# FDD_3.net
KiCad netlist of a schematic drawn in Altium Designer
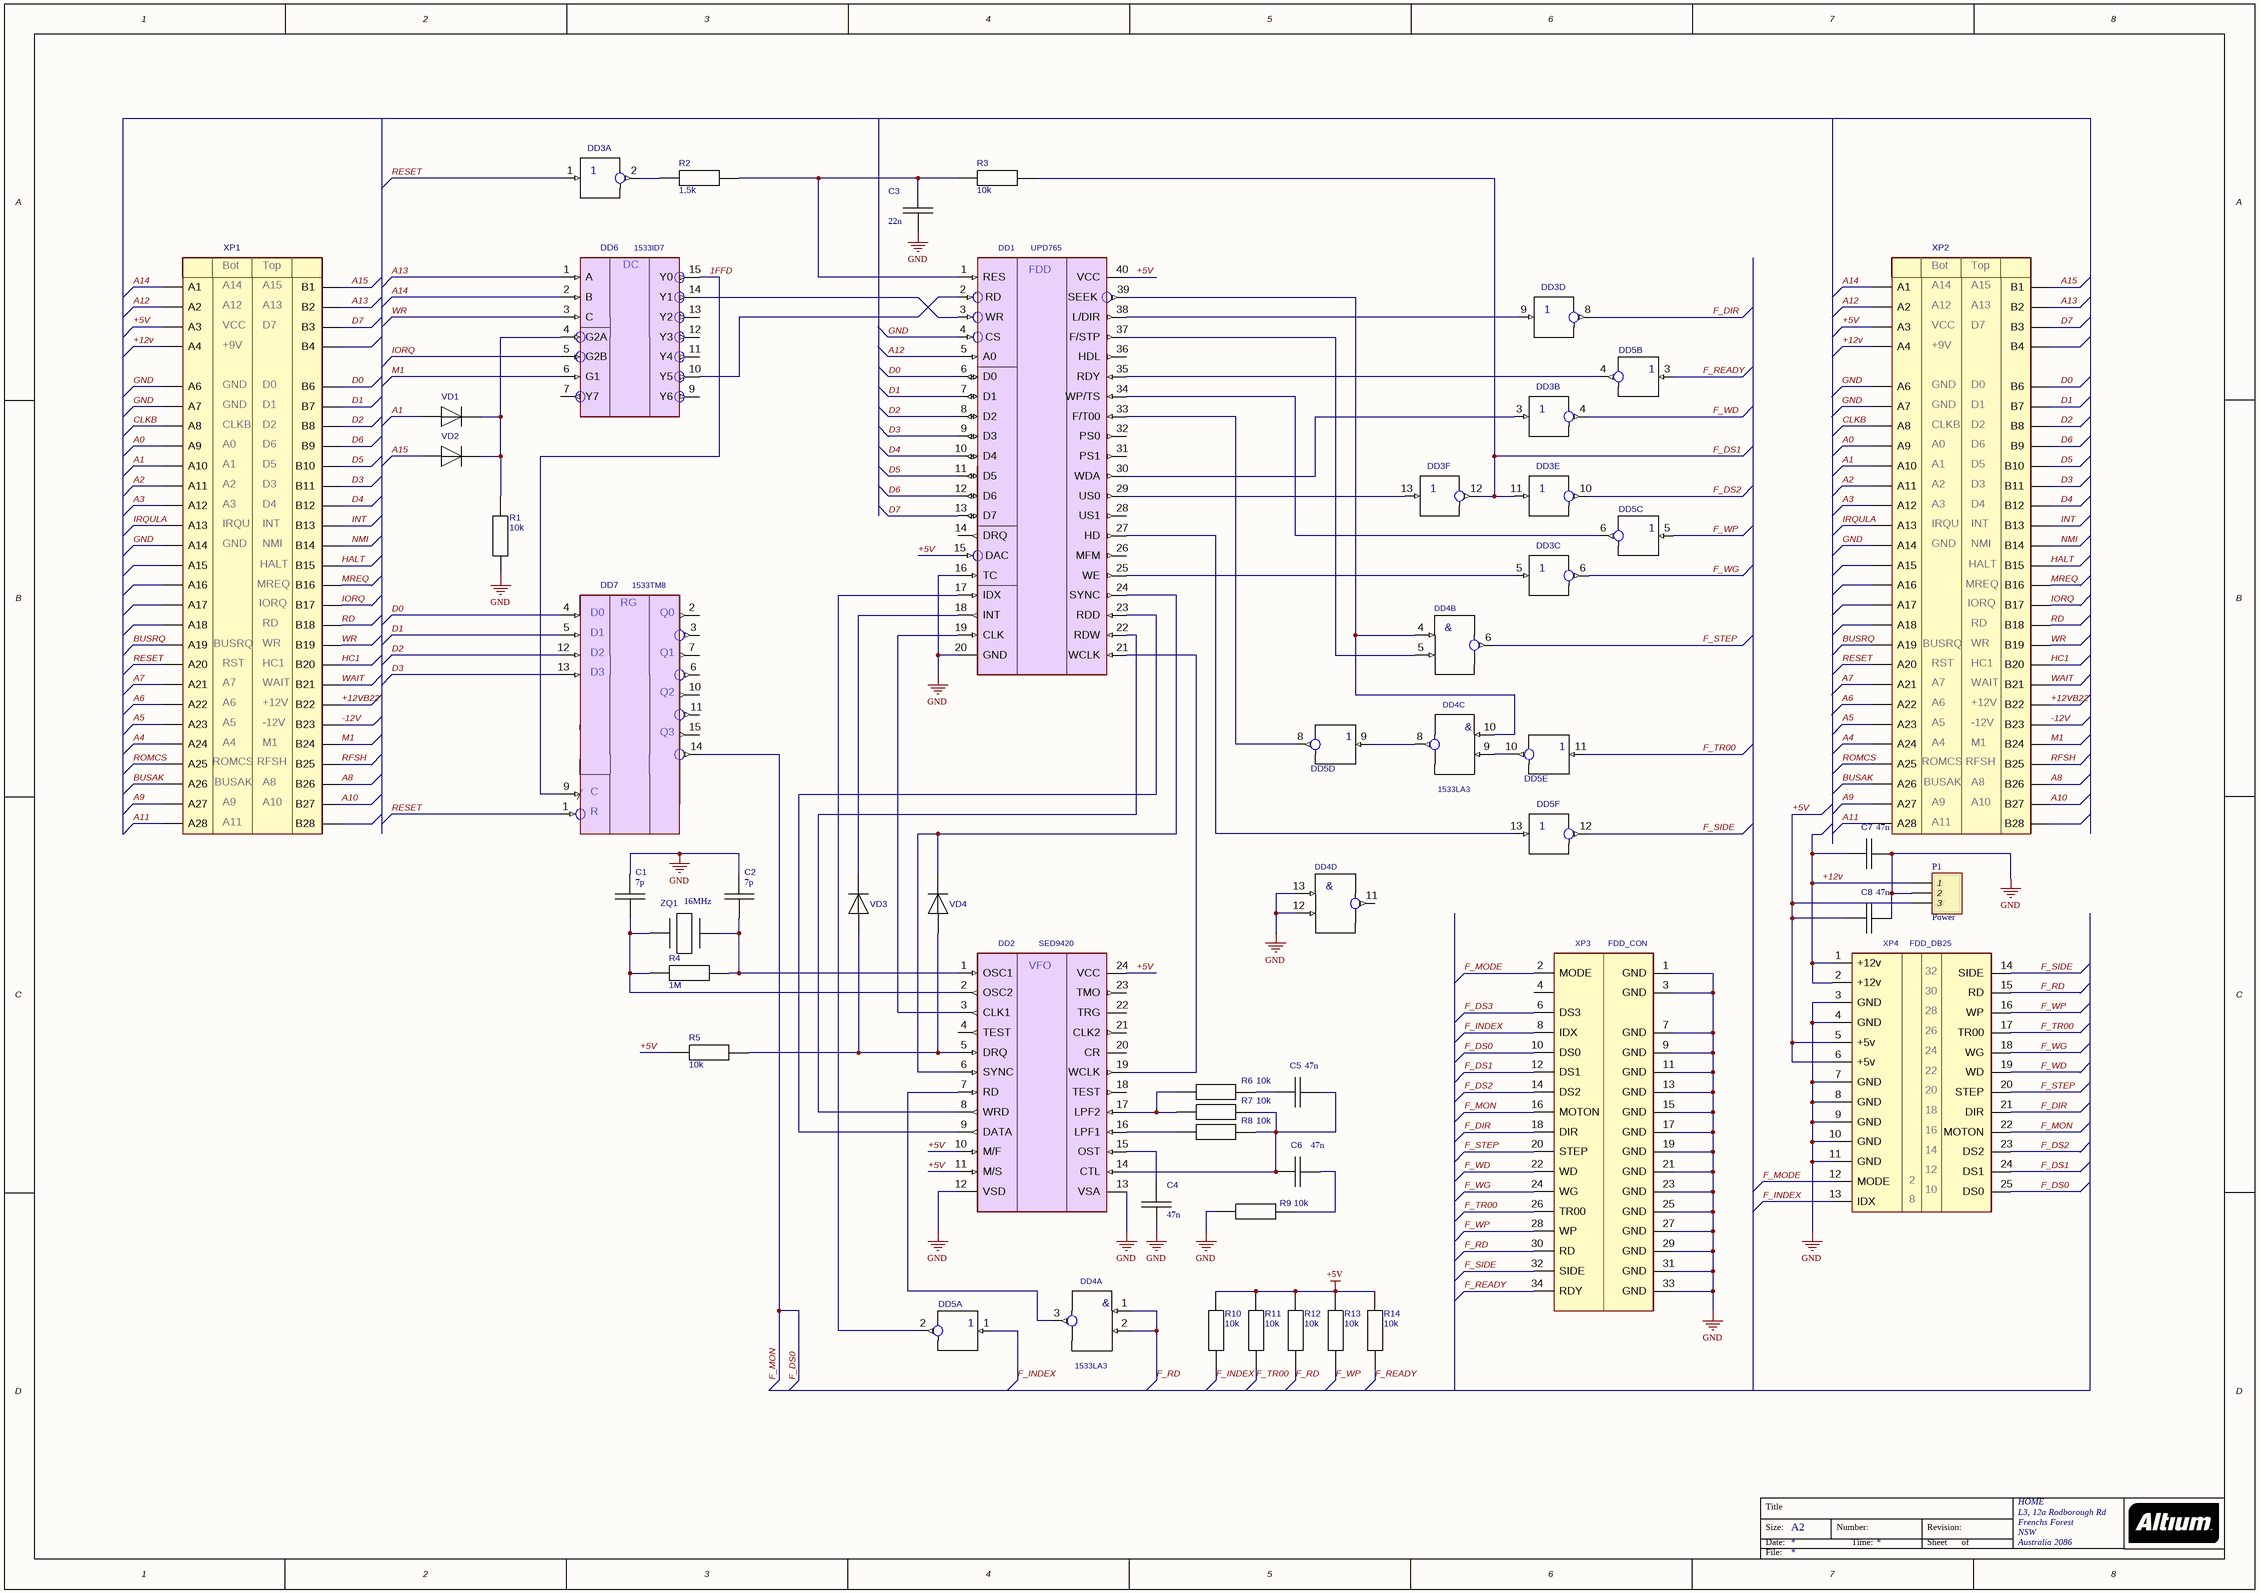
[diagram p0: FDD+3.SchDoc]

(export (version "E")
  (design (tool "Eeschema 10.0.6"))
  (components
    (comp (ref "C1")
      (value "7p")
      (footprint "K10-17_75")
      (fields (field (name "Comment") "K10-17_75"))
      (libsource (lib "Pentagon") (part "K10-17_75"))
    )
    (comp (ref "C2")
      (value "7p")
      (footprint "K10-17_75")
      (fields (field (name "Comment") "K10-17_75"))
      (libsource (lib "Pentagon") (part "K10-17_75"))
    )
    (comp (ref "C3")
      (value "22n")
      (footprint "K10-17_75")
      (fields (field (name "Comment") "K10-17_75"))
      (libsource (lib "Pentagon") (part "K10-17_75"))
    )
    (comp (ref "C4")
      (value "47n")
      (footprint "K10-17_75")
      (fields (field (name "Comment") "K10-17_75"))
      (libsource (lib "Pentagon") (part "K10-17_75"))
    )
    (comp (ref "C5")
      (value "47n")
      (footprint "K10-17_75")
      (fields (field (name "Comment") "K10-17_75"))
      (libsource (lib "Pentagon") (part "K10-17_75"))
    )
    (comp (ref "C6")
      (value "47n")
      (footprint "K10-17_75")
      (fields (field (name "Comment") "K10-17_75"))
      (libsource (lib "Pentagon") (part "K10-17_75"))
    )
    (comp (ref "C7")
      (value "47n")
      (footprint "K10-17_75")
      (fields (field (name "Comment") "K10-17_75"))
      (libsource (lib "Pentagon") (part "K10-17_75"))
    )
    (comp (ref "C8")
      (value "47n")
      (footprint "K10-17_75")
      (fields (field (name "Comment") "K10-17_75"))
      (libsource (lib "Pentagon") (part "K10-17_75"))
    )
    (comp (ref "DD1") (value "UPD765") (footprint "DIP40_15") (libsource (lib "Pentagon") (part "UPD765")))
    (comp (ref "DD2") (value "SED9420") (footprint "DIP24_15") (libsource (lib "Pentagon") (part "SED9420")))
    (comp (ref "DD3") (value "1533LN1") (footprint "DIP14") (libsource (lib "") (part "1533LN1_1")))
    (comp (ref "DD4") (value "1533LA3") (footprint "DIP14") (libsource (lib "Pentagon") (part "1533LA3")))
    (comp (ref "DD5") (value "1533LN1") (footprint "DIP14") (libsource (lib "") (part "1533LN1_5")))
    (comp (ref "DD6") (value "1533ID7") (footprint "DIP16") (libsource (lib "Pentagon") (part "1533ID7")))
    (comp (ref "DD7") (value "1533TM8") (footprint "DIP16") (libsource (lib "Pentagon") (part "1533TM8")))
    (comp (ref "P1")
      (value "Power")
      (footprint "HDR1X3")
      (description "Header, 3-Pin")
      (fields (field (name "PUBLISHER") "Altium Limited"))
      (libsource (lib "Miscellaneous Connectors") (part "Header 3"))
    )
    (comp (ref "R1")
      (value "10k")
      (footprint "R0125-2_5")
      (fields (field (name "Comment") "R0125-2_5"))
      (libsource (lib "Pentagon") (part "R0125-2_5"))
    )
    (comp (ref "R2")
      (value "1,5k")
      (footprint "R0125-2_5")
      (fields (field (name "Comment") "R0125-2_5"))
      (libsource (lib "Pentagon") (part "R0125-2_5"))
    )
    (comp (ref "R3")
      (value "10k")
      (footprint "R0125-2_5")
      (fields (field (name "Comment") "R0125-2_5"))
      (libsource (lib "Pentagon") (part "R0125-2_5"))
    )
    (comp (ref "R4")
      (value "1M")
      (footprint "R0125-2_5")
      (fields (field (name "Comment") "R0125-2_5"))
      (libsource (lib "Pentagon") (part "R0125-2_5"))
    )
    (comp (ref "R5")
      (value "10k")
      (footprint "R0125-2_5")
      (fields (field (name "Comment") "R0125-2_5"))
      (libsource (lib "Pentagon") (part "R0125-2_5"))
    )
    (comp (ref "R6")
      (value "10k")
      (footprint "R0125-2_5")
      (fields (field (name "Comment") "R0125-2_5"))
      (libsource (lib "Pentagon") (part "R0125-2_5"))
    )
    (comp (ref "R7")
      (value "10k")
      (footprint "R0125-2_5")
      (fields (field (name "Comment") "R0125-2_5"))
      (libsource (lib "Pentagon") (part "R0125-2_5"))
    )
    (comp (ref "R8")
      (value "10k")
      (footprint "R0125-2_5")
      (fields (field (name "Comment") "R0125-2_5"))
      (libsource (lib "Pentagon") (part "R0125-2_5"))
    )
    (comp (ref "R9")
      (value "10k")
      (footprint "R0125-2_5")
      (fields (field (name "Comment") "R0125-2_5"))
      (libsource (lib "Pentagon") (part "R0125-2_5"))
    )
    (comp (ref "R10")
      (value "10k")
      (footprint "R0125-2_5")
      (fields (field (name "Comment") "R0125-2_5"))
      (libsource (lib "Pentagon") (part "R0125-2_5"))
    )
    (comp (ref "R11")
      (value "10k")
      (footprint "R0125-2_5")
      (fields (field (name "Comment") "R0125-2_5"))
      (libsource (lib "Pentagon") (part "R0125-2_5"))
    )
    (comp (ref "R12")
      (value "10k")
      (footprint "R0125-2_5")
      (fields (field (name "Comment") "R0125-2_5"))
      (libsource (lib "Pentagon") (part "R0125-2_5"))
    )
    (comp (ref "R13")
      (value "10k")
      (footprint "R0125-2_5")
      (fields (field (name "Comment") "R0125-2_5"))
      (libsource (lib "Pentagon") (part "R0125-2_5"))
    )
    (comp (ref "R14")
      (value "10k")
      (footprint "R0125-2_5")
      (fields (field (name "Comment") "R0125-2_5"))
      (libsource (lib "Pentagon") (part "R0125-2_5"))
    )
    (comp (ref "VD1")
      (value "KD522-2_5")
      (footprint "KD522-2_5")
      (libsource (lib "Pentagon") (part "KD522-2_5"))
    )
    (comp (ref "VD2")
      (value "KD522-2_5")
      (footprint "KD522-2_5")
      (libsource (lib "Pentagon") (part "KD522-2_5"))
    )
    (comp (ref "VD3")
      (value "KD522-2_5")
      (footprint "KD522-2_5")
      (libsource (lib "Pentagon") (part "KD522-2_5"))
    )
    (comp (ref "VD4")
      (value "KD522-2_5")
      (footprint "KD522-2_5")
      (libsource (lib "Pentagon") (part "KD522-2_5"))
    )
    (comp (ref "XP1") (value "ZX EDGE") (footprint "ZX_EDGE") (libsource (lib "Pentagon") (part "ZX EDGE")))
    (comp (ref "XP2") (value "ZX EDGE") (footprint "ZX_EDGE") (libsource (lib "Pentagon") (part "ZX EDGE")))
    (comp (ref "XP3")
      (value "FDD_CON")
      (footprint "FDD_CON_Male")
      (libsource (lib "Pentagon") (part "FDD_CON"))
    )
    (comp (ref "XP4")
      (value "FDD_DB25")
      (footprint "DSUB1.385-2H25A")
      (libsource (lib "Pentagon") (part "FDD_DB25"))
    )
    (comp (ref "ZQ1")
      (value "16MHz")
      (footprint "RK169MD")
      (fields (field (name "Comment") "RK169MD"))
      (libsource (lib "Pentagon") (part "RK169MD"))
    )
  )
  (nets
    (net (code "1") (name "+5V") (class "Default")
      (node (ref "C8") (pin "2") (pinfunction "B_2") (pintype "passive"))
      (node (ref "DD1") (pin "15") (pinfunction "DAC_15") (pintype "input"))
      (node (ref "DD1") (pin "40") (pinfunction "VCC_40") (pintype "power_in"))
      (node (ref "DD2") (pin "10") (pinfunction "M/F_10") (pintype "input"))
      (node (ref "DD2") (pin "11") (pinfunction "M/S_11") (pintype "input"))
      (node (ref "DD2") (pin "24") (pinfunction "VCC_24") (pintype "power_in"))
      (node (ref "DD3") (pin "14") (pinfunction "+5V_14") (pintype "power_in"))
      (node (ref "DD4") (pin "14") (pinfunction "+5V_14") (pintype "power_in"))
      (node (ref "DD5") (pin "14") (pinfunction "+5V_14") (pintype "power_in"))
      (node (ref "DD6") (pin "16") (pinfunction "+5V_16") (pintype "power_in"))
      (node (ref "DD7") (pin "16") (pinfunction "+5V_16") (pintype "power_in"))
      (node (ref "P1") (pin "3") (pinfunction "3_3") (pintype "passive"))
      (node (ref "R10") (pin "1") (pinfunction "A_1") (pintype "passive"))
      (node (ref "R11") (pin "1") (pinfunction "A_1") (pintype "passive"))
      (node (ref "R12") (pin "1") (pinfunction "A_1") (pintype "passive"))
      (node (ref "R13") (pin "1") (pinfunction "A_1") (pintype "passive"))
      (node (ref "R14") (pin "1") (pinfunction "A_1") (pintype "passive"))
      (node (ref "R5") (pin "2") (pinfunction "B_2") (pintype "passive"))
      (node (ref "XP1") (pin "3") (pinfunction "A3_3") (pintype "power_in"))
      (node (ref "XP2") (pin "3") (pinfunction "A3_3") (pintype "power_in"))
      (node (ref "XP4") (pin "5") (pinfunction "+5v_5") (pintype "passive"))
      (node (ref "XP4") (pin "6") (pinfunction "+5v_6") (pintype "passive"))
    )
    (net (code "2") (name "/+12VB22") (class "Default")
      (node (ref "XP1") (pin "50") (pinfunction "B22_50") (pintype "passive"))
      (node (ref "XP2") (pin "50") (pinfunction "B22_50") (pintype "passive"))
    )
    (net (code "3") (name "/+12v") (class "Default")
      (node (ref "C7") (pin "2") (pinfunction "B_2") (pintype "passive"))
      (node (ref "P1") (pin "1") (pinfunction "1_1") (pintype "passive"))
      (node (ref "XP1") (pin "4") (pinfunction "A4_4") (pintype "passive"))
      (node (ref "XP2") (pin "4") (pinfunction "A4_4") (pintype "passive"))
      (node (ref "XP4") (pin "1") (pinfunction "+12v_1") (pintype "passive"))
      (node (ref "XP4") (pin "2") (pinfunction "+12v_2") (pintype "passive"))
    )
    (net (code "4") (name "/-12V") (class "Default")
      (node (ref "XP1") (pin "51") (pinfunction "B23_51") (pintype "passive"))
      (node (ref "XP2") (pin "51") (pinfunction "B23_51") (pintype "passive"))
    )
    (net (code "5") (name "/1FFD") (class "Default")
      (node (ref "DD6") (pin "15") (pinfunction "Y0_15") (pintype "output"))
      (node (ref "DD7") (pin "9") (pinfunction "C_9") (pintype "input"))
    )
    (net (code "6") (name "/A0") (class "Default")
      (node (ref "XP1") (pin "9") (pinfunction "A9_9") (pintype "passive"))
      (node (ref "XP2") (pin "9") (pinfunction "A9_9") (pintype "passive"))
    )
    (net (code "7") (name "/A1") (class "Default")
      (node (ref "VD1") (pin "1") (pinfunction "A_1") (pintype "passive"))
      (node (ref "XP1") (pin "10") (pinfunction "A10_10") (pintype "passive"))
      (node (ref "XP2") (pin "10") (pinfunction "A10_10") (pintype "passive"))
    )
    (net (code "8") (name "/A2") (class "Default")
      (node (ref "XP1") (pin "11") (pinfunction "A11_11") (pintype "passive"))
      (node (ref "XP2") (pin "11") (pinfunction "A11_11") (pintype "passive"))
    )
    (net (code "9") (name "/A3") (class "Default")
      (node (ref "XP1") (pin "12") (pinfunction "A12_12") (pintype "passive"))
      (node (ref "XP2") (pin "12") (pinfunction "A12_12") (pintype "passive"))
    )
    (net (code "10") (name "/A4") (class "Default")
      (node (ref "XP1") (pin "24") (pinfunction "A24_24") (pintype "passive"))
      (node (ref "XP2") (pin "24") (pinfunction "A24_24") (pintype "passive"))
    )
    (net (code "11") (name "/A5") (class "Default")
      (node (ref "XP1") (pin "23") (pinfunction "A23_23") (pintype "passive"))
      (node (ref "XP2") (pin "23") (pinfunction "A23_23") (pintype "passive"))
    )
    (net (code "12") (name "/A6") (class "Default")
      (node (ref "XP1") (pin "22") (pinfunction "A22_22") (pintype "passive"))
      (node (ref "XP2") (pin "22") (pinfunction "A22_22") (pintype "passive"))
    )
    (net (code "13") (name "/A7") (class "Default")
      (node (ref "XP1") (pin "21") (pinfunction "A21_21") (pintype "passive"))
      (node (ref "XP2") (pin "21") (pinfunction "A21_21") (pintype "passive"))
    )
    (net (code "14") (name "/A8") (class "Default")
      (node (ref "XP1") (pin "54") (pinfunction "B26_54") (pintype "passive"))
      (node (ref "XP2") (pin "54") (pinfunction "B26_54") (pintype "passive"))
    )
    (net (code "15") (name "/A9") (class "Default")
      (node (ref "XP1") (pin "27") (pinfunction "A27_27") (pintype "passive"))
      (node (ref "XP2") (pin "27") (pinfunction "A27_27") (pintype "passive"))
    )
    (net (code "16") (name "/A10") (class "Default")
      (node (ref "XP1") (pin "55") (pinfunction "B27_55") (pintype "passive"))
      (node (ref "XP2") (pin "55") (pinfunction "B27_55") (pintype "passive"))
    )
    (net (code "17") (name "/A11") (class "Default")
      (node (ref "XP1") (pin "28") (pinfunction "A28_28") (pintype "passive"))
      (node (ref "XP2") (pin "28") (pinfunction "A28_28") (pintype "passive"))
    )
    (net (code "18") (name "/A12") (class "Default")
      (node (ref "DD1") (pin "5") (pinfunction "A0_5") (pintype "input"))
      (node (ref "XP1") (pin "2") (pinfunction "A2_2") (pintype "passive"))
      (node (ref "XP2") (pin "2") (pinfunction "A2_2") (pintype "passive"))
    )
    (net (code "19") (name "/A13") (class "Default")
      (node (ref "DD6") (pin "1") (pinfunction "A_1") (pintype "input"))
      (node (ref "XP1") (pin "30") (pinfunction "B2_30") (pintype "passive"))
      (node (ref "XP2") (pin "30") (pinfunction "B2_30") (pintype "passive"))
    )
    (net (code "20") (name "/A14") (class "Default")
      (node (ref "DD6") (pin "2") (pinfunction "B_2") (pintype "input"))
      (node (ref "XP1") (pin "1") (pinfunction "A1_1") (pintype "passive"))
      (node (ref "XP2") (pin "1") (pinfunction "A1_1") (pintype "passive"))
    )
    (net (code "21") (name "/A15") (class "Default")
      (node (ref "VD2") (pin "1") (pinfunction "A_1") (pintype "passive"))
      (node (ref "XP1") (pin "29") (pinfunction "B1_29") (pintype "passive"))
      (node (ref "XP2") (pin "29") (pinfunction "B1_29") (pintype "passive"))
    )
    (net (code "22") (name "/BUSAK") (class "Default")
      (node (ref "XP1") (pin "26") (pinfunction "A26_26") (pintype "passive"))
      (node (ref "XP2") (pin "26") (pinfunction "A26_26") (pintype "passive"))
    )
    (net (code "23") (name "/BUSRQ") (class "Default")
      (node (ref "XP1") (pin "19") (pinfunction "A19_19") (pintype "passive"))
      (node (ref "XP2") (pin "19") (pinfunction "A19_19") (pintype "passive"))
    )
    (net (code "24") (name "/CLKB") (class "Default")
      (node (ref "XP1") (pin "8") (pinfunction "A8_8") (pintype "passive"))
      (node (ref "XP2") (pin "8") (pinfunction "A8_8") (pintype "passive"))
    )
    (net (code "25") (name "/D0") (class "Default")
      (node (ref "DD1") (pin "6") (pinfunction "D0_6") (pintype "bidirectional"))
      (node (ref "DD7") (pin "4") (pinfunction "D0_4") (pintype "input"))
      (node (ref "XP1") (pin "34") (pinfunction "B6_34") (pintype "passive"))
      (node (ref "XP2") (pin "34") (pinfunction "B6_34") (pintype "passive"))
    )
    (net (code "26") (name "/D1") (class "Default")
      (node (ref "DD1") (pin "7") (pinfunction "D1_7") (pintype "bidirectional"))
      (node (ref "DD7") (pin "5") (pinfunction "D1_5") (pintype "input"))
      (node (ref "XP1") (pin "35") (pinfunction "B7_35") (pintype "passive"))
      (node (ref "XP2") (pin "35") (pinfunction "B7_35") (pintype "passive"))
    )
    (net (code "27") (name "/D2") (class "Default")
      (node (ref "DD1") (pin "8") (pinfunction "D2_8") (pintype "bidirectional"))
      (node (ref "DD7") (pin "12") (pinfunction "D2_12") (pintype "input"))
      (node (ref "XP1") (pin "36") (pinfunction "B8_36") (pintype "passive"))
      (node (ref "XP2") (pin "36") (pinfunction "B8_36") (pintype "passive"))
    )
    (net (code "28") (name "/D3") (class "Default")
      (node (ref "DD1") (pin "9") (pinfunction "D3_9") (pintype "bidirectional"))
      (node (ref "DD7") (pin "13") (pinfunction "D3_13") (pintype "input"))
      (node (ref "XP1") (pin "39") (pinfunction "B11_39") (pintype "passive"))
      (node (ref "XP2") (pin "39") (pinfunction "B11_39") (pintype "passive"))
    )
    (net (code "29") (name "/D4") (class "Default")
      (node (ref "DD1") (pin "10") (pinfunction "D4_10") (pintype "bidirectional"))
      (node (ref "XP1") (pin "40") (pinfunction "B12_40") (pintype "passive"))
      (node (ref "XP2") (pin "40") (pinfunction "B12_40") (pintype "passive"))
    )
    (net (code "30") (name "/D5") (class "Default")
      (node (ref "DD1") (pin "11") (pinfunction "D5_11") (pintype "bidirectional"))
      (node (ref "XP1") (pin "38") (pinfunction "B10_38") (pintype "passive"))
      (node (ref "XP2") (pin "38") (pinfunction "B10_38") (pintype "passive"))
    )
    (net (code "31") (name "/D6") (class "Default")
      (node (ref "DD1") (pin "12") (pinfunction "D6_12") (pintype "bidirectional"))
      (node (ref "XP1") (pin "37") (pinfunction "B9_37") (pintype "passive"))
      (node (ref "XP2") (pin "37") (pinfunction "B9_37") (pintype "passive"))
    )
    (net (code "32") (name "/D7") (class "Default")
      (node (ref "DD1") (pin "13") (pinfunction "D7_13") (pintype "bidirectional"))
      (node (ref "XP1") (pin "31") (pinfunction "B3_31") (pintype "passive"))
      (node (ref "XP2") (pin "31") (pinfunction "B3_31") (pintype "passive"))
    )
    (net (code "33") (name "/F_DIR") (class "Default")
      (node (ref "DD3") (pin "8") (pinfunction "B_8") (pintype "output"))
      (node (ref "XP3") (pin "18") (pinfunction "DIR_18") (pintype "passive"))
      (node (ref "XP4") (pin "21") (pinfunction "DIR_21") (pintype "passive"))
    )
    (net (code "34") (name "/F_DS0") (class "Default")
      (node (ref "DD7") (pin "14") (pinfunction "Q4/_14") (pintype "output"))
      (node (ref "XP3") (pin "10") (pinfunction "DS0_10") (pintype "passive"))
      (node (ref "XP3") (pin "16") (pinfunction "MOTON_16") (pintype "passive"))
      (node (ref "XP4") (pin "22") (pinfunction "MOTON_22") (pintype "passive"))
      (node (ref "XP4") (pin "25") (pinfunction "DS0_25") (pintype "passive"))
    )
    (net (code "35") (name "/F_DS1") (class "Default")
      (node (ref "DD3") (pin "11") (pinfunction "A_11") (pintype "input"))
      (node (ref "DD3") (pin "12") (pinfunction "B_12") (pintype "output"))
      (node (ref "R3") (pin "1") (pinfunction "A_1") (pintype "passive"))
      (node (ref "XP3") (pin "12") (pinfunction "DS1_12") (pintype "passive"))
      (node (ref "XP4") (pin "24") (pinfunction "DS1_24") (pintype "passive"))
    )
    (net (code "36") (name "/F_DS2") (class "Default")
      (node (ref "DD3") (pin "10") (pinfunction "B_10") (pintype "output"))
      (node (ref "XP3") (pin "14") (pinfunction "DS2_14") (pintype "passive"))
      (node (ref "XP4") (pin "23") (pinfunction "DS2_23") (pintype "passive"))
    )
    (net (code "37") (name "/F_DS3") (class "Default")
      (node (ref "XP3") (pin "6") (pinfunction "DS3_6") (pintype "passive"))
    )
    (net (code "38") (name "/F_INDEX") (class "Default")
      (node (ref "DD5") (pin "1") (pinfunction "A_1") (pintype "input"))
      (node (ref "R10") (pin "2") (pinfunction "B_2") (pintype "passive"))
      (node (ref "XP3") (pin "8") (pinfunction "IDX_8") (pintype "passive"))
      (node (ref "XP4") (pin "13") (pinfunction "IDX_13") (pintype "passive"))
    )
    (net (code "39") (name "/F_MODE") (class "Default")
      (node (ref "XP3") (pin "2") (pinfunction "MODE_2") (pintype "passive"))
      (node (ref "XP4") (pin "12") (pinfunction "MODE_12") (pintype "passive"))
    )
    (net (code "40") (name "/F_RD") (class "Default")
      (node (ref "DD4") (pin "1") (pinfunction "A_1") (pintype "input"))
      (node (ref "DD4") (pin "2") (pinfunction "B_2") (pintype "input"))
      (node (ref "R12") (pin "2") (pinfunction "B_2") (pintype "passive"))
      (node (ref "XP3") (pin "30") (pinfunction "RD_30") (pintype "passive"))
      (node (ref "XP4") (pin "15") (pinfunction "RD_15") (pintype "passive"))
    )
    (net (code "41") (name "/F_READY") (class "Default")
      (node (ref "DD5") (pin "3") (pinfunction "A_3") (pintype "input"))
      (node (ref "R14") (pin "2") (pinfunction "B_2") (pintype "passive"))
      (node (ref "XP3") (pin "34") (pinfunction "RDY_34") (pintype "passive"))
    )
    (net (code "42") (name "/F_SIDE") (class "Default")
      (node (ref "DD5") (pin "12") (pinfunction "B_12") (pintype "output"))
      (node (ref "XP3") (pin "32") (pinfunction "SIDE_32") (pintype "passive"))
      (node (ref "XP4") (pin "14") (pinfunction "SIDE_14") (pintype "passive"))
    )
    (net (code "43") (name "/F_STEP") (class "Default")
      (node (ref "DD4") (pin "6") (pinfunction "C_6") (pintype "output"))
      (node (ref "XP3") (pin "20") (pinfunction "STEP_20") (pintype "passive"))
      (node (ref "XP4") (pin "20") (pinfunction "STEP_20") (pintype "passive"))
    )
    (net (code "44") (name "/F_TR00") (class "Default")
      (node (ref "DD5") (pin "11") (pinfunction "A_11") (pintype "input"))
      (node (ref "R11") (pin "2") (pinfunction "B_2") (pintype "passive"))
      (node (ref "XP3") (pin "26") (pinfunction "TR00_26") (pintype "passive"))
      (node (ref "XP4") (pin "17") (pinfunction "TR00_17") (pintype "passive"))
    )
    (net (code "45") (name "/F_WD") (class "Default")
      (node (ref "DD3") (pin "4") (pinfunction "B_4") (pintype "output"))
      (node (ref "XP3") (pin "22") (pinfunction "WD_22") (pintype "passive"))
      (node (ref "XP4") (pin "19") (pinfunction "WD_19") (pintype "passive"))
    )
    (net (code "46") (name "/F_WG") (class "Default")
      (node (ref "DD3") (pin "6") (pinfunction "B_6") (pintype "output"))
      (node (ref "XP3") (pin "24") (pinfunction "WG_24") (pintype "passive"))
      (node (ref "XP4") (pin "18") (pinfunction "WG_18") (pintype "passive"))
    )
    (net (code "47") (name "/F_WP") (class "Default")
      (node (ref "DD5") (pin "5") (pinfunction "A_5") (pintype "input"))
      (node (ref "R13") (pin "2") (pinfunction "B_2") (pintype "passive"))
      (node (ref "XP3") (pin "28") (pinfunction "WP_28") (pintype "passive"))
      (node (ref "XP4") (pin "16") (pinfunction "WP_16") (pintype "passive"))
    )
    (net (code "48") (name "/HALT") (class "Default")
      (node (ref "XP1") (pin "43") (pinfunction "B15_43") (pintype "passive"))
      (node (ref "XP2") (pin "43") (pinfunction "B15_43") (pintype "passive"))
    )
    (net (code "49") (name "/HC1") (class "Default")
      (node (ref "XP1") (pin "48") (pinfunction "B20_48") (pintype "passive"))
      (node (ref "XP2") (pin "48") (pinfunction "B20_48") (pintype "passive"))
    )
    (net (code "50") (name "/INT") (class "Default")
      (node (ref "XP1") (pin "41") (pinfunction "B13_41") (pintype "passive"))
      (node (ref "XP2") (pin "41") (pinfunction "B13_41") (pintype "passive"))
    )
    (net (code "51") (name "/IORQ") (class "Default")
      (node (ref "DD6") (pin "5") (pinfunction "G2B_5") (pintype "input"))
      (node (ref "XP1") (pin "45") (pinfunction "B17_45") (pintype "passive"))
      (node (ref "XP2") (pin "45") (pinfunction "B17_45") (pintype "passive"))
    )
    (net (code "52") (name "/IRQULA") (class "Default")
      (node (ref "XP1") (pin "13") (pinfunction "A13_13") (pintype "passive"))
      (node (ref "XP2") (pin "13") (pinfunction "A13_13") (pintype "passive"))
    )
    (net (code "53") (name "/M1") (class "Default")
      (node (ref "DD6") (pin "6") (pinfunction "G1_6") (pintype "input"))
      (node (ref "XP1") (pin "52") (pinfunction "B24_52") (pintype "passive"))
      (node (ref "XP2") (pin "52") (pinfunction "B24_52") (pintype "passive"))
    )
    (net (code "54") (name "/MREQ") (class "Default")
      (node (ref "XP1") (pin "44") (pinfunction "B16_44") (pintype "passive"))
      (node (ref "XP2") (pin "44") (pinfunction "B16_44") (pintype "passive"))
    )
    (net (code "55") (name "/NMI") (class "Default")
      (node (ref "XP1") (pin "42") (pinfunction "B14_42") (pintype "passive"))
      (node (ref "XP2") (pin "42") (pinfunction "B14_42") (pintype "passive"))
    )
    (net (code "56") (name "/RD") (class "Default")
      (node (ref "XP1") (pin "46") (pinfunction "B18_46") (pintype "passive"))
      (node (ref "XP2") (pin "46") (pinfunction "B18_46") (pintype "passive"))
    )
    (net (code "57") (name "/RESET") (class "Default")
      (node (ref "DD3") (pin "1") (pinfunction "A_1") (pintype "input"))
      (node (ref "DD7") (pin "1") (pinfunction "R_1") (pintype "input"))
      (node (ref "XP1") (pin "20") (pinfunction "A20_20") (pintype "passive"))
      (node (ref "XP2") (pin "20") (pinfunction "A20_20") (pintype "passive"))
    )
    (net (code "58") (name "/RFSH") (class "Default")
      (node (ref "XP1") (pin "53") (pinfunction "B25_53") (pintype "passive"))
      (node (ref "XP2") (pin "53") (pinfunction "B25_53") (pintype "passive"))
    )
    (net (code "59") (name "/ROMCS") (class "Default")
      (node (ref "XP1") (pin "25") (pinfunction "A25_25") (pintype "passive"))
      (node (ref "XP2") (pin "25") (pinfunction "A25_25") (pintype "passive"))
    )
    (net (code "60") (name "/WAIT") (class "Default")
      (node (ref "XP1") (pin "49") (pinfunction "B21_49") (pintype "passive"))
      (node (ref "XP2") (pin "49") (pinfunction "B21_49") (pintype "passive"))
    )
    (net (code "61") (name "/WR") (class "Default")
      (node (ref "DD6") (pin "3") (pinfunction "C_3") (pintype "input"))
      (node (ref "XP1") (pin "47") (pinfunction "B19_47") (pintype "passive"))
      (node (ref "XP2") (pin "47") (pinfunction "B19_47") (pintype "passive"))
    )
    (net (code "62") (name "GND") (class "Default")
      (node (ref "C1") (pin "2") (pinfunction "B_2") (pintype "passive"))
      (node (ref "C2") (pin "2") (pinfunction "B_2") (pintype "passive"))
      (node (ref "C3") (pin "1") (pinfunction "A_1") (pintype "passive"))
      (node (ref "C4") (pin "1") (pinfunction "A_1") (pintype "passive"))
      (node (ref "C7") (pin "1") (pinfunction "A_1") (pintype "passive"))
      (node (ref "C8") (pin "1") (pinfunction "A_1") (pintype "passive"))
      (node (ref "DD1") (pin "16") (pinfunction "TC_16") (pintype "input"))
      (node (ref "DD1") (pin "20") (pinfunction "GND_20") (pintype "power_in"))
      (node (ref "DD1") (pin "4") (pinfunction "CS_4") (pintype "input"))
      (node (ref "DD2") (pin "12") (pinfunction "VSD_12") (pintype "power_in"))
      (node (ref "DD2") (pin "13") (pinfunction "VSA_13") (pintype "power_in"))
      (node (ref "DD3") (pin "7") (pinfunction "GND_7") (pintype "power_in"))
      (node (ref "DD4") (pin "12") (pinfunction "B_12") (pintype "input"))
      (node (ref "DD4") (pin "13") (pinfunction "A_13") (pintype "input"))
      (node (ref "DD4") (pin "7") (pinfunction "GND_7") (pintype "power_in"))
      (node (ref "DD5") (pin "7") (pinfunction "GND_7") (pintype "power_in"))
      (node (ref "DD6") (pin "8") (pinfunction "GND_8") (pintype "power_in"))
      (node (ref "DD7") (pin "8") (pinfunction "GND_8") (pintype "power_in"))
      (node (ref "P1") (pin "2") (pinfunction "2_2") (pintype "passive"))
      (node (ref "R1") (pin "1") (pinfunction "A_1") (pintype "passive"))
      (node (ref "R9") (pin "2") (pinfunction "B_2") (pintype "passive"))
      (node (ref "XP1") (pin "14") (pinfunction "A14_14") (pintype "power_in"))
      (node (ref "XP1") (pin "6") (pinfunction "A6_6") (pintype "power_in"))
      (node (ref "XP1") (pin "7") (pinfunction "A7_7") (pintype "power_in"))
      (node (ref "XP2") (pin "14") (pinfunction "A14_14") (pintype "power_in"))
      (node (ref "XP2") (pin "6") (pinfunction "A6_6") (pintype "power_in"))
      (node (ref "XP2") (pin "7") (pinfunction "A7_7") (pintype "power_in"))
      (node (ref "XP3") (pin "1") (pinfunction "GND_1") (pintype "passive"))
      (node (ref "XP3") (pin "11") (pinfunction "GND_11") (pintype "passive"))
      (node (ref "XP3") (pin "13") (pinfunction "GND_13") (pintype "passive"))
      (node (ref "XP3") (pin "15") (pinfunction "GND_15") (pintype "passive"))
      (node (ref "XP3") (pin "17") (pinfunction "GND_17") (pintype "passive"))
      (node (ref "XP3") (pin "19") (pinfunction "GND_19") (pintype "passive"))
      (node (ref "XP3") (pin "21") (pinfunction "GND_21") (pintype "passive"))
      (node (ref "XP3") (pin "23") (pinfunction "GND_23") (pintype "passive"))
      (node (ref "XP3") (pin "25") (pinfunction "GND_25") (pintype "passive"))
      (node (ref "XP3") (pin "27") (pinfunction "GND_27") (pintype "passive"))
      (node (ref "XP3") (pin "29") (pinfunction "GND_29") (pintype "passive"))
      (node (ref "XP3") (pin "3") (pinfunction "GND_3") (pintype "passive"))
      (node (ref "XP3") (pin "31") (pinfunction "GND_31") (pintype "passive"))
      (node (ref "XP3") (pin "33") (pinfunction "GND_33") (pintype "passive"))
      (node (ref "XP3") (pin "7") (pinfunction "GND_7") (pintype "passive"))
      (node (ref "XP3") (pin "9") (pinfunction "GND_9") (pintype "passive"))
      (node (ref "XP4") (pin "10") (pinfunction "GND_10") (pintype "passive"))
      (node (ref "XP4") (pin "11") (pinfunction "GND_11") (pintype "passive"))
      (node (ref "XP4") (pin "3") (pinfunction "GND_3") (pintype "passive"))
      (node (ref "XP4") (pin "4") (pinfunction "GND_4") (pintype "passive"))
      (node (ref "XP4") (pin "7") (pinfunction "GND_7") (pintype "passive"))
      (node (ref "XP4") (pin "8") (pinfunction "GND_8") (pintype "passive"))
      (node (ref "XP4") (pin "9") (pinfunction "GND_9") (pintype "passive"))
    )
    (net (code "63") (name "Net-(C1-A)") (class "Default")
      (node (ref "C1") (pin "1") (pinfunction "A_1") (pintype "passive"))
      (node (ref "DD2") (pin "2") (pinfunction "OSC2_2") (pintype "output"))
      (node (ref "R4") (pin "2") (pinfunction "B_2") (pintype "passive"))
      (node (ref "ZQ1") (pin "1") (pinfunction "A_1") (pintype "passive"))
    )
    (net (code "64") (name "Net-(C2-A)") (class "Default")
      (node (ref "C2") (pin "1") (pinfunction "A_1") (pintype "passive"))
      (node (ref "DD2") (pin "1") (pinfunction "OSC1_1") (pintype "input"))
      (node (ref "R4") (pin "1") (pinfunction "A_1") (pintype "passive"))
      (node (ref "ZQ1") (pin "2") (pinfunction "B_2") (pintype "passive"))
    )
    (net (code "65") (name "Net-(C3-B)") (class "Default")
      (node (ref "C3") (pin "2") (pinfunction "B_2") (pintype "passive"))
      (node (ref "DD1") (pin "1") (pinfunction "RES_1") (pintype "input"))
      (node (ref "R2") (pin "1") (pinfunction "A_1") (pintype "passive"))
      (node (ref "R3") (pin "2") (pinfunction "B_2") (pintype "passive"))
    )
    (net (code "66") (name "Net-(C4-B)") (class "Default")
      (node (ref "C4") (pin "2") (pinfunction "B_2") (pintype "passive"))
      (node (ref "DD2") (pin "15") (pinfunction "OST_15") (pintype "input"))
    )
    (net (code "67") (name "Net-(C5-A)") (class "Default")
      (node (ref "C5") (pin "1") (pinfunction "A_1") (pintype "passive"))
      (node (ref "C6") (pin "2") (pinfunction "B_2") (pintype "passive"))
      (node (ref "DD2") (pin "14") (pinfunction "CTL_14") (pintype "input"))
      (node (ref "R7") (pin "1") (pinfunction "A_1") (pintype "passive"))
      (node (ref "R8") (pin "1") (pinfunction "A_1") (pintype "passive"))
    )
    (net (code "68") (name "Net-(C5-B)") (class "Default")
      (node (ref "C5") (pin "2") (pinfunction "B_2") (pintype "passive"))
      (node (ref "R6") (pin "1") (pinfunction "A_1") (pintype "passive"))
    )
    (net (code "69") (name "Net-(C6-A)") (class "Default")
      (node (ref "C6") (pin "1") (pinfunction "A_1") (pintype "passive"))
      (node (ref "R9") (pin "1") (pinfunction "A_1") (pintype "passive"))
    )
    (net (code "70") (name "Net-(DD1-CLK)") (class "Default")
      (node (ref "DD1") (pin "19") (pinfunction "CLK_19") (pintype "input"))
      (node (ref "DD2") (pin "3") (pinfunction "CLK1_3") (pintype "output"))
    )
    (net (code "71") (name "Net-(DD1-F{slash}STP)") (class "Default")
      (node (ref "DD1") (pin "37") (pinfunction "F/STP_37") (pintype "output"))
      (node (ref "DD4") (pin "5") (pinfunction "B_5") (pintype "input"))
    )
    (net (code "72") (name "Net-(DD1-F{slash}T00)") (class "Default")
      (node (ref "DD1") (pin "33") (pinfunction "F/T00_33") (pintype "input"))
      (node (ref "DD5") (pin "8") (pinfunction "B_8") (pintype "output"))
    )
    (net (code "73") (name "Net-(DD1-HD)") (class "Default")
      (node (ref "DD1") (pin "27") (pinfunction "HD_27") (pintype "output"))
      (node (ref "DD5") (pin "13") (pinfunction "A_13") (pintype "input"))
    )
    (net (code "74") (name "Net-(DD1-IDX)") (class "Default")
      (node (ref "DD1") (pin "17") (pinfunction "IDX_17") (pintype "input"))
      (node (ref "DD5") (pin "2") (pinfunction "B_2") (pintype "output"))
    )
    (net (code "75") (name "Net-(DD1-INT)") (class "Default")
      (node (ref "DD1") (pin "18") (pinfunction "INT_18") (pintype "output"))
      (node (ref "VD3") (pin "2") (pinfunction "B_2") (pintype "passive"))
    )
    (net (code "76") (name "Net-(DD1-L{slash}DIR)") (class "Default")
      (node (ref "DD1") (pin "38") (pinfunction "L/DIR_38") (pintype "output"))
      (node (ref "DD3") (pin "9") (pinfunction "A_9") (pintype "input"))
    )
    (net (code "77") (name "Net-(DD1-RD)") (class "Default")
      (node (ref "DD1") (pin "2") (pinfunction "RD_2") (pintype "input"))
      (node (ref "DD6") (pin "10") (pinfunction "Y5_10") (pintype "output"))
    )
    (net (code "78") (name "Net-(DD1-RDD)") (class "Default")
      (node (ref "DD1") (pin "23") (pinfunction "RDD_23") (pintype "input"))
      (node (ref "DD2") (pin "9") (pinfunction "DATA_9") (pintype "output"))
    )
    (net (code "79") (name "Net-(DD1-RDW)") (class "Default")
      (node (ref "DD1") (pin "22") (pinfunction "RDW_22") (pintype "input"))
      (node (ref "DD2") (pin "8") (pinfunction "WRD_8") (pintype "output"))
    )
    (net (code "80") (name "Net-(DD1-RDY)") (class "Default")
      (node (ref "DD1") (pin "35") (pinfunction "RDY_35") (pintype "input"))
      (node (ref "DD5") (pin "4") (pinfunction "B_4") (pintype "output"))
    )
    (net (code "81") (name "Net-(DD1-SEEK)") (class "Default")
      (node (ref "DD1") (pin "39") (pinfunction "SEEK_39") (pintype "output"))
      (node (ref "DD4") (pin "10") (pinfunction "A_10") (pintype "input"))
      (node (ref "DD4") (pin "4") (pinfunction "A_4") (pintype "input"))
    )
    (net (code "82") (name "Net-(DD1-SYNC)") (class "Default")
      (node (ref "DD1") (pin "24") (pinfunction "SYNC_24") (pintype "output"))
      (node (ref "DD2") (pin "6") (pinfunction "SYNC_6") (pintype "input"))
      (node (ref "VD4") (pin "2") (pinfunction "B_2") (pintype "passive"))
    )
    (net (code "83") (name "Net-(DD1-US0)") (class "Default")
      (node (ref "DD1") (pin "29") (pinfunction "US0_29") (pintype "output"))
      (node (ref "DD3") (pin "13") (pinfunction "A_13") (pintype "input"))
    )
    (net (code "84") (name "Net-(DD1-WCLK)") (class "Default")
      (node (ref "DD1") (pin "21") (pinfunction "WCLK_21") (pintype "input"))
      (node (ref "DD2") (pin "19") (pinfunction "WCLK_19") (pintype "output"))
    )
    (net (code "85") (name "Net-(DD1-WDA)") (class "Default")
      (node (ref "DD1") (pin "30") (pinfunction "WDA_30") (pintype "output"))
      (node (ref "DD3") (pin "3") (pinfunction "A_3") (pintype "input"))
    )
    (net (code "86") (name "Net-(DD1-WE)") (class "Default")
      (node (ref "DD1") (pin "25") (pinfunction "WE_25") (pintype "output"))
      (node (ref "DD3") (pin "5") (pinfunction "A_5") (pintype "input"))
    )
    (net (code "87") (name "Net-(DD1-WP{slash}TS)") (class "Default")
      (node (ref "DD1") (pin "34") (pinfunction "WP/TS_34") (pintype "input"))
      (node (ref "DD5") (pin "6") (pinfunction "B_6") (pintype "output"))
    )
    (net (code "88") (name "Net-(DD1-WR)") (class "Default")
      (node (ref "DD1") (pin "3") (pinfunction "WR_3") (pintype "input"))
      (node (ref "DD6") (pin "14") (pinfunction "Y1_14") (pintype "output"))
    )
    (net (code "89") (name "Net-(DD2-DRQ)") (class "Default")
      (node (ref "DD2") (pin "5") (pinfunction "DRQ_5") (pintype "input"))
      (node (ref "R5") (pin "1") (pinfunction "A_1") (pintype "passive"))
      (node (ref "VD3") (pin "1") (pinfunction "A_1") (pintype "passive"))
      (node (ref "VD4") (pin "1") (pinfunction "A_1") (pintype "passive"))
    )
    (net (code "90") (name "Net-(DD2-LPF1)") (class "Default")
      (node (ref "DD2") (pin "16") (pinfunction "LPF1_16") (pintype "input"))
      (node (ref "R8") (pin "2") (pinfunction "B_2") (pintype "passive"))
    )
    (net (code "91") (name "Net-(DD2-LPF2)") (class "Default")
      (node (ref "DD2") (pin "17") (pinfunction "LPF2_17") (pintype "input"))
      (node (ref "R6") (pin "2") (pinfunction "B_2") (pintype "passive"))
      (node (ref "R7") (pin "2") (pinfunction "B_2") (pintype "passive"))
    )
    (net (code "92") (name "Net-(DD2-RD)") (class "Default")
      (node (ref "DD2") (pin "7") (pinfunction "RD_7") (pintype "input"))
      (node (ref "DD4") (pin "3") (pinfunction "C_3") (pintype "output"))
    )
    (net (code "93") (name "Net-(DD3A-B)") (class "Default")
      (node (ref "DD3") (pin "2") (pinfunction "B_2") (pintype "output"))
      (node (ref "R2") (pin "2") (pinfunction "B_2") (pintype "passive"))
    )
    (net (code "94") (name "Net-(DD4C-B)") (class "Default")
      (node (ref "DD4") (pin "9") (pinfunction "B_9") (pintype "input"))
      (node (ref "DD5") (pin "10") (pinfunction "B_10") (pintype "output"))
    )
    (net (code "95") (name "Net-(DD4C-C)") (class "Default")
      (node (ref "DD4") (pin "8") (pinfunction "C_8") (pintype "output"))
      (node (ref "DD5") (pin "9") (pinfunction "A_9") (pintype "input"))
    )
    (net (code "96") (name "Net-(DD6-G2A)") (class "Default")
      (node (ref "DD6") (pin "4") (pinfunction "G2A_4") (pintype "input"))
      (node (ref "R1") (pin "2") (pinfunction "B_2") (pintype "passive"))
      (node (ref "VD1") (pin "2") (pinfunction "B_2") (pintype "passive"))
      (node (ref "VD2") (pin "2") (pinfunction "B_2") (pintype "passive"))
    )
    (net (code "97") (name "unconnected-(DD1-DRQ-Pad14)") (class "Default")
      (node (ref "DD1") (pin "14") (pinfunction "DRQ_14") (pintype "output"))
    )
    (net (code "98") (name "unconnected-(DD1-HDL-Pad36)") (class "Default")
      (node (ref "DD1") (pin "36") (pinfunction "HDL_36") (pintype "output"))
    )
    (net (code "99") (name "unconnected-(DD1-MFM-Pad26)") (class "Default")
      (node (ref "DD1") (pin "26") (pinfunction "MFM_26") (pintype "output"))
    )
    (net (code "100") (name "unconnected-(DD1-PS0-Pad32)") (class "Default")
      (node (ref "DD1") (pin "32") (pinfunction "PS0_32") (pintype "output"))
    )
    (net (code "101") (name "unconnected-(DD1-PS1-Pad31)") (class "Default")
      (node (ref "DD1") (pin "31") (pinfunction "PS1_31") (pintype "output"))
    )
    (net (code "102") (name "unconnected-(DD1-US1-Pad28)") (class "Default")
      (node (ref "DD1") (pin "28") (pinfunction "US1_28") (pintype "output"))
    )
    (net (code "103") (name "unconnected-(DD2-CLK2-Pad21)") (class "Default")
      (node (ref "DD2") (pin "21") (pinfunction "CLK2_21") (pintype "output"))
    )
    (net (code "104") (name "unconnected-(DD2-CR-Pad20)") (class "Default")
      (node (ref "DD2") (pin "20") (pinfunction "CR_20") (pintype "passive"))
    )
    (net (code "105") (name "unconnected-(DD2-TEST-Pad4)") (class "Default")
      (node (ref "DD2") (pin "4") (pinfunction "TEST_4") (pintype "output"))
    )
    (net (code "106") (name "unconnected-(DD2-TEST-Pad18)") (class "Default")
      (node (ref "DD2") (pin "18") (pinfunction "TEST_18") (pintype "output"))
    )
    (net (code "107") (name "unconnected-(DD2-TMO-Pad23)") (class "Default")
      (node (ref "DD2") (pin "23") (pinfunction "TMO_23") (pintype "output"))
    )
    (net (code "108") (name "unconnected-(DD2-TRG-Pad22)") (class "Default")
      (node (ref "DD2") (pin "22") (pinfunction "TRG_22") (pintype "passive"))
    )
    (net (code "109") (name "unconnected-(DD4D-C-Pad11)") (class "Default")
      (node (ref "DD4") (pin "11") (pinfunction "C_11") (pintype "output"))
    )
    (net (code "110") (name "unconnected-(DD6-Y2-Pad13)") (class "Default")
      (node (ref "DD6") (pin "13") (pinfunction "Y2_13") (pintype "output"))
    )
    (net (code "111") (name "unconnected-(DD6-Y3-Pad12)") (class "Default")
      (node (ref "DD6") (pin "12") (pinfunction "Y3_12") (pintype "output"))
    )
    (net (code "112") (name "unconnected-(DD6-Y4-Pad11)") (class "Default")
      (node (ref "DD6") (pin "11") (pinfunction "Y4_11") (pintype "output"))
    )
    (net (code "113") (name "unconnected-(DD6-Y6-Pad9)") (class "Default")
      (node (ref "DD6") (pin "9") (pinfunction "Y6_9") (pintype "output"))
    )
    (net (code "114") (name "unconnected-(DD6-Y7-Pad7)") (class "Default")
      (node (ref "DD6") (pin "7") (pinfunction "Y7_7") (pintype "output"))
    )
    (net (code "115") (name "unconnected-(DD7-Q0-Pad2)") (class "Default")
      (node (ref "DD7") (pin "2") (pinfunction "Q0_2") (pintype "output"))
    )
    (net (code "116") (name "unconnected-(DD7-Q0{slash}-Pad3)") (class "Default")
      (node (ref "DD7") (pin "3") (pinfunction "Q0/_3") (pintype "output"))
    )
    (net (code "117") (name "unconnected-(DD7-Q1-Pad7)") (class "Default")
      (node (ref "DD7") (pin "7") (pinfunction "Q1_7") (pintype "output"))
    )
    (net (code "118") (name "unconnected-(DD7-Q1{slash}-Pad6)") (class "Default")
      (node (ref "DD7") (pin "6") (pinfunction "Q1/_6") (pintype "output"))
    )
    (net (code "119") (name "unconnected-(DD7-Q2-Pad10)") (class "Default")
      (node (ref "DD7") (pin "10") (pinfunction "Q2_10") (pintype "output"))
    )
    (net (code "120") (name "unconnected-(DD7-Q2{slash}-Pad11)") (class "Default")
      (node (ref "DD7") (pin "11") (pinfunction "Q2/_11") (pintype "output"))
    )
    (net (code "121") (name "unconnected-(DD7-Q4-Pad15)") (class "Default")
      (node (ref "DD7") (pin "15") (pinfunction "Q4_15") (pintype "output"))
    )
    (net (code "122") (name "unconnected-(XP1-A15-Pad15)") (class "Default")
      (node (ref "XP1") (pin "15") (pinfunction "A15_15") (pintype "passive"))
    )
    (net (code "123") (name "unconnected-(XP1-A16-Pad16)") (class "Default")
      (node (ref "XP1") (pin "16") (pinfunction "A16_16") (pintype "passive"))
    )
    (net (code "124") (name "unconnected-(XP1-A17-Pad17)") (class "Default")
      (node (ref "XP1") (pin "17") (pinfunction "A17_17") (pintype "passive"))
    )
    (net (code "125") (name "unconnected-(XP1-A18-Pad18)") (class "Default")
      (node (ref "XP1") (pin "18") (pinfunction "A18_18") (pintype "passive"))
    )
    (net (code "126") (name "unconnected-(XP1-B4-Pad32)") (class "Default")
      (node (ref "XP1") (pin "32") (pinfunction "B4_32") (pintype "passive"))
    )
    (net (code "127") (name "unconnected-(XP1-B28-Pad56)") (class "Default")
      (node (ref "XP1") (pin "56") (pinfunction "B28_56") (pintype "passive"))
    )
    (net (code "128") (name "unconnected-(XP2-A15-Pad15)") (class "Default")
      (node (ref "XP2") (pin "15") (pinfunction "A15_15") (pintype "passive"))
    )
    (net (code "129") (name "unconnected-(XP2-A16-Pad16)") (class "Default")
      (node (ref "XP2") (pin "16") (pinfunction "A16_16") (pintype "passive"))
    )
    (net (code "130") (name "unconnected-(XP2-A17-Pad17)") (class "Default")
      (node (ref "XP2") (pin "17") (pinfunction "A17_17") (pintype "passive"))
    )
    (net (code "131") (name "unconnected-(XP2-A18-Pad18)") (class "Default")
      (node (ref "XP2") (pin "18") (pinfunction "A18_18") (pintype "passive"))
    )
    (net (code "132") (name "unconnected-(XP2-B4-Pad32)") (class "Default")
      (node (ref "XP2") (pin "32") (pinfunction "B4_32") (pintype "passive"))
    )
    (net (code "133") (name "unconnected-(XP2-B28-Pad56)") (class "Default")
      (node (ref "XP2") (pin "56") (pinfunction "B28_56") (pintype "passive"))
    )
    (net (code "134") (name "unconnected-(XP3-Pad4)") (class "Default")
      (node (ref "XP3") (pin "4") (pintype "passive"))
    )
    (net (code "135") (name "unconnected-(XP4-Pad26)") (class "Default")
      (node (ref "XP4") (pin "26") (pintype "passive"))
    )
    (net (code "136") (name "unconnected-(XP4-Pad27)") (class "Default")
      (node (ref "XP4") (pin "27") (pintype "passive"))
    )
    (net (code "137") (name "unconnected-(XP4-Pad28)") (class "Default")
      (node (ref "XP4") (pin "28") (pintype "passive"))
    )
    (net (code "138") (name "unconnected-(XP4-Pad29)") (class "Default")
      (node (ref "XP4") (pin "29") (pintype "passive"))
    )
    (net (code "139") (name "unconnected-(XP4-Pad30)") (class "Default")
      (node (ref "XP4") (pin "30") (pintype "passive"))
    )
    (net (code "140") (name "unconnected-(XP4-Pad31)") (class "Default")
      (node (ref "XP4") (pin "31") (pintype "passive"))
    )
    (net (code "141") (name "unconnected-(XP4-Pad32)") (class "Default")
      (node (ref "XP4") (pin "32") (pintype "passive"))
    )
    (net (code "142") (name "unconnected-(XP4-Pad33)") (class "Default")
      (node (ref "XP4") (pin "33") (pintype "passive"))
    )
    (net (code "143") (name "unconnected-(XP4-Pad34)") (class "Default")
      (node (ref "XP4") (pin "34") (pintype "passive"))
    )
    (net (code "144") (name "unconnected-(XP4-Pad35)") (class "Default")
      (node (ref "XP4") (pin "35") (pintype "passive"))
    )
    (net (code "145") (name "unconnected-(XP4-Pad36)") (class "Default")
      (node (ref "XP4") (pin "36") (pintype "passive"))
    )
    (net (code "146") (name "unconnected-(XP4-Pad37)") (class "Default")
      (node (ref "XP4") (pin "37") (pintype "passive"))
    )
    (net (code "147") (name "unconnected-(XP4-Pad38)") (class "Default")
      (node (ref "XP4") (pin "38") (pintype "passive"))
    )
    (net (code "148") (name "unconnected-(XP4-Pad39)") (class "Default")
      (node (ref "XP4") (pin "39") (pintype "passive"))
    )
    (net (code "149") (name "unconnected-(XP4-Pad40)") (class "Default")
      (node (ref "XP4") (pin "40") (pintype "passive"))
    )
    (net (code "150") (name "unconnected-(XP4-Pad41)") (class "Default")
      (node (ref "XP4") (pin "41") (pintype "passive"))
    )
    (net (code "151") (name "unconnected-(XP4-Pad42)") (class "Default")
      (node (ref "XP4") (pin "42") (pintype "passive"))
    )
    (net (code "152") (name "unconnected-(XP4-Pad43)") (class "Default")
      (node (ref "XP4") (pin "43") (pintype "passive"))
    )
    (net (code "153") (name "unconnected-(XP4-Pad44)") (class "Default")
      (node (ref "XP4") (pin "44") (pintype "passive"))
    )
    (net (code "154") (name "unconnected-(XP4-Pad45)") (class "Default")
      (node (ref "XP4") (pin "45") (pintype "passive"))
    )
    (net (code "155") (name "unconnected-(XP4-Pad46)") (class "Default")
      (node (ref "XP4") (pin "46") (pintype "passive"))
    )
    (net (code "156") (name "unconnected-(XP4-Pad47)") (class "Default")
      (node (ref "XP4") (pin "47") (pintype "passive"))
    )
    (net (code "157") (name "unconnected-(XP4-Pad48)") (class "Default")
      (node (ref "XP4") (pin "48") (pintype "passive"))
    )
    (net (code "158") (name "unconnected-(XP4-Pad49)") (class "Default")
      (node (ref "XP4") (pin "49") (pintype "passive"))
    )
    (net (code "159") (name "unconnected-(XP4-Pad50)") (class "Default")
      (node (ref "XP4") (pin "50") (pintype "passive"))
    )
  )
)
